# 8_-DAC_and_MIC.net
KiCad netlist of a schematic drawn in Altium Designer
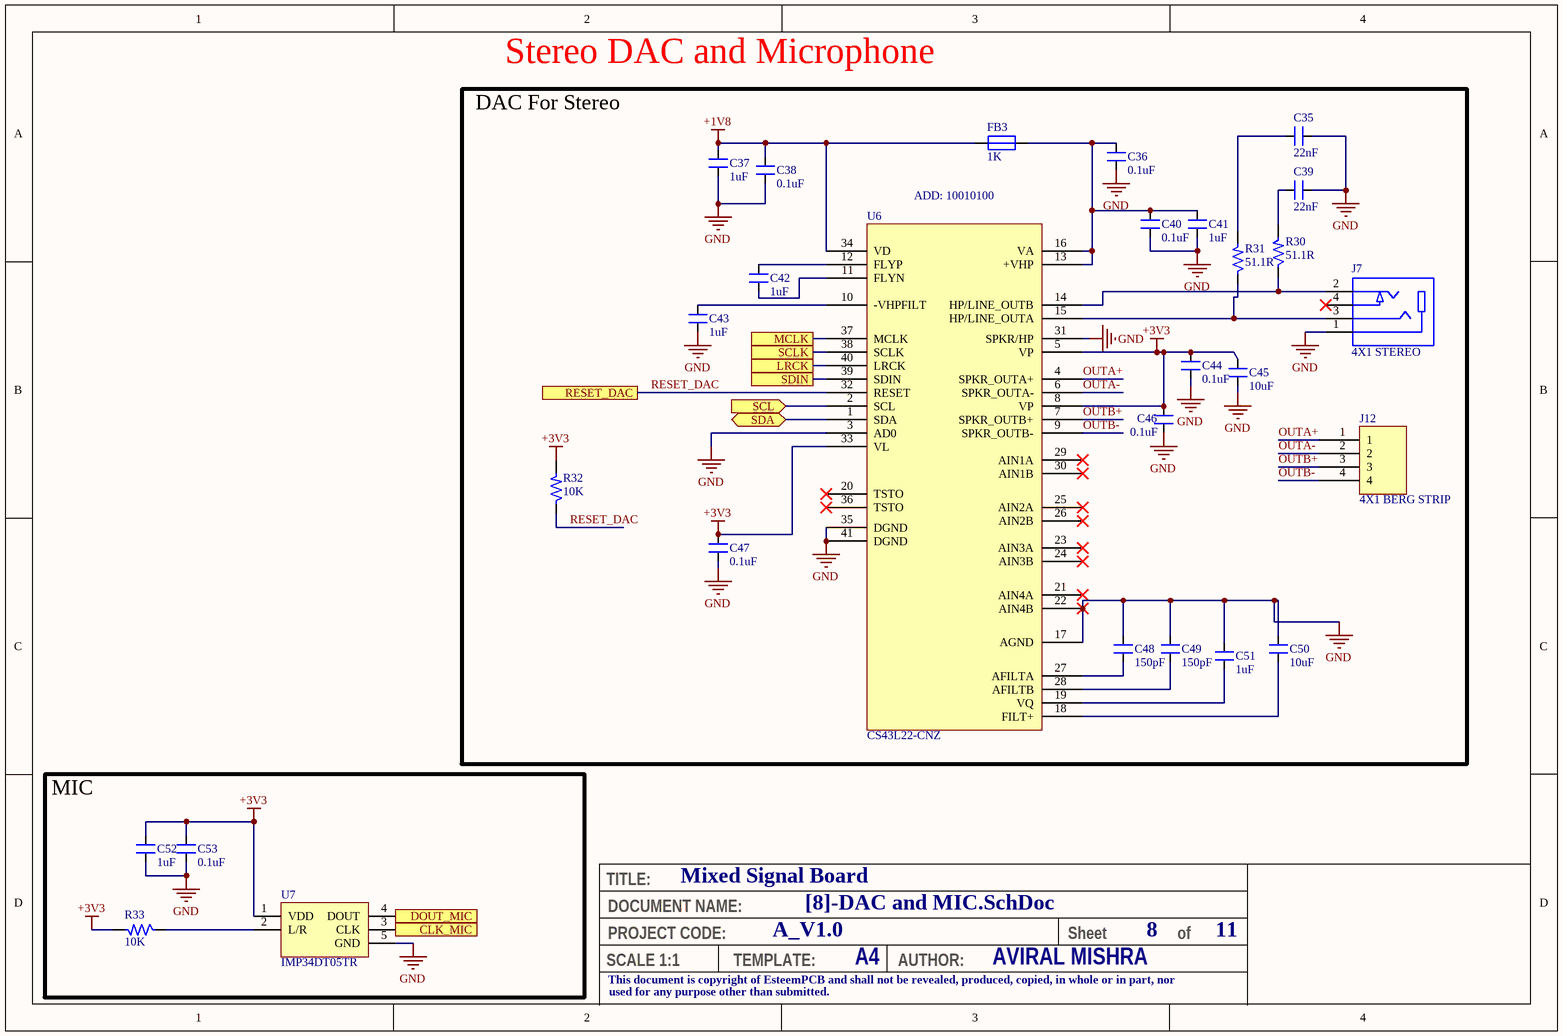
[diagram p0: [8]-DAC and MIC.SchDoc]

(export (version "E")
  (design (tool "Eeschema 10.0.6"))
  (components
    (comp (ref "C35")
      (value "22nF")
      (footprint "CAP_0805")
      (description "0.022µF ±10% 50V Ceramic Capacitor X7R 0805 (2012 Metric)")
      (fields
        (field (name "MANUFACTURER") "Samsung Electro-Mechanics")
        (field (name "MANUFACTURER PART NUMBER") "CL21B223KBANNNC")
      )
      (libsource (lib "ESTEEMPCBLIB") (part "CAP_22nF-50V-10%-0805"))
    )
    (comp (ref "C36")
      (value "0.1uF")
      (footprint "CAP_0805")
      (description "0.1µF ±10% 50V Ceramic Capacitor X7R 0805 (2012 Metric)")
      (fields
        (field (name "MANUFACTURER") "Samsung")
        (field (name "MANUFACTURER PART NUMBER") "CL21B104KBCNNNC")
      )
      (libsource (lib "ESTEEMPCBLIB") (part "CAP_0.1uF-50V-10%-0805"))
    )
    (comp (ref "C37")
      (value "1uF")
      (footprint "CAP_0805")
      (description "1µF ±5% 50V Ceramic Capacitor X7R 0805 (2012 Metric)")
      (fields
        (field (name "MANUFACTURER") "Samsung")
        (field (name "MANUFACTURER PART NUMBER") "CC0805JKX7R9BB105")
      )
      (libsource (lib "ESTEEMPCBLIB") (part "CAP_1uF-50V-5%-0805"))
    )
    (comp (ref "C38")
      (value "0.1uF")
      (footprint "CAP_0805")
      (description "0.1µF ±10% 50V Ceramic Capacitor X7R 0805 (2012 Metric)")
      (fields
        (field (name "MANUFACTURER") "Samsung")
        (field (name "MANUFACTURER PART NUMBER") "CL21B104KBCNNNC")
      )
      (libsource (lib "ESTEEMPCBLIB") (part "CAP_0.1uF-50V-10%-0805"))
    )
    (comp (ref "C39")
      (value "22nF")
      (footprint "CAP_0805")
      (description "0.022µF ±10% 50V Ceramic Capacitor X7R 0805 (2012 Metric)")
      (fields
        (field (name "MANUFACTURER") "Samsung Electro-Mechanics")
        (field (name "MANUFACTURER PART NUMBER") "CL21B223KBANNNC")
      )
      (libsource (lib "ESTEEMPCBLIB") (part "CAP_22nF-50V-10%-0805"))
    )
    (comp (ref "C40")
      (value "0.1uF")
      (footprint "CAP_0805")
      (description "0.1µF ±10% 50V Ceramic Capacitor X7R 0805 (2012 Metric)")
      (fields
        (field (name "MANUFACTURER") "Samsung")
        (field (name "MANUFACTURER PART NUMBER") "CL21B104KBCNNNC")
      )
      (libsource (lib "ESTEEMPCBLIB") (part "CAP_0.1uF-50V-10%-0805"))
    )
    (comp (ref "C41")
      (value "1uF")
      (footprint "CAP_0805")
      (description "1µF ±5% 50V Ceramic Capacitor X7R 0805 (2012 Metric)")
      (fields
        (field (name "MANUFACTURER") "Samsung")
        (field (name "MANUFACTURER PART NUMBER") "CC0805JKX7R9BB105")
      )
      (libsource (lib "ESTEEMPCBLIB") (part "CAP_1uF-50V-5%-0805"))
    )
    (comp (ref "C42")
      (value "1uF")
      (footprint "CAP_0805")
      (description "1µF ±5% 50V Ceramic Capacitor X7R 0805 (2012 Metric)")
      (fields
        (field (name "MANUFACTURER") "Samsung")
        (field (name "MANUFACTURER PART NUMBER") "CC0805JKX7R9BB105")
      )
      (libsource (lib "ESTEEMPCBLIB") (part "CAP_1uF-50V-5%-0805"))
    )
    (comp (ref "C43")
      (value "1uF")
      (footprint "CAP_0805")
      (description "1µF ±5% 50V Ceramic Capacitor X7R 0805 (2012 Metric)")
      (fields
        (field (name "MANUFACTURER") "Samsung")
        (field (name "MANUFACTURER PART NUMBER") "CC0805JKX7R9BB105")
      )
      (libsource (lib "ESTEEMPCBLIB") (part "CAP_1uF-50V-5%-0805"))
    )
    (comp (ref "C44")
      (value "0.1uF")
      (footprint "CAP_0805")
      (description "0.1µF ±10% 50V Ceramic Capacitor X7R 0805 (2012 Metric)")
      (fields
        (field (name "MANUFACTURER") "Samsung")
        (field (name "MANUFACTURER PART NUMBER") "CL21B104KBCNNNC")
      )
      (libsource (lib "ESTEEMPCBLIB") (part "CAP_0.1uF-50V-10%-0805"))
    )
    (comp (ref "C45")
      (value "10uF")
      (footprint "CAP_1206")
      (description "10µF ±10% 50V Ceramic Capacitor X7R 1206 (3216 Metric)")
      (fields
        (field (name "MANUFACTURER") "KEMET")
        (field (name "MANUFACTURER PART NUMBER") "CL31B106KBHNNNE")
      )
      (libsource (lib "ESTEEMPCBLIB") (part "CAP_10uF-50V-10%-1206"))
    )
    (comp (ref "C46")
      (value "0.1uF")
      (footprint "CAP_0805")
      (description "0.1µF ±10% 50V Ceramic Capacitor X7R 0805 (2012 Metric)")
      (fields
        (field (name "MANUFACTURER") "Samsung")
        (field (name "MANUFACTURER PART NUMBER") "CL21B104KBCNNNC")
      )
      (libsource (lib "ESTEEMPCBLIB") (part "CAP_0.1uF-50V-10%-0805"))
    )
    (comp (ref "C47")
      (value "0.1uF")
      (footprint "CAP_0805")
      (description "0.1µF ±10% 50V Ceramic Capacitor X7R 0805 (2012 Metric)")
      (fields
        (field (name "MANUFACTURER") "Samsung")
        (field (name "MANUFACTURER PART NUMBER") "CL21B104KBCNNNC")
      )
      (libsource (lib "ESTEEMPCBLIB") (part "CAP_0.1uF-50V-10%-0805"))
    )
    (comp (ref "C48")
      (value "150pF")
      (footprint "CAP_0805")
      (description "150pF ±10% 50V Ceramic Capacitor C0G, NP0 0805 (2012 Metric)")
      (fields
        (field (name "MANUFACTURER") "AVX Corporation")
        (field (name "MANUFACTURER PART NUMBER") "08055A151KAT2A")
      )
      (libsource (lib "ESTEEMPCBLIB") (part "CAP_150pF-50V-10%-0805"))
    )
    (comp (ref "C49")
      (value "150pF")
      (footprint "CAP_0805")
      (description "150pF ±10% 50V Ceramic Capacitor C0G, NP0 0805 (2012 Metric)")
      (fields
        (field (name "MANUFACTURER") "AVX Corporation")
        (field (name "MANUFACTURER PART NUMBER") "08055A151KAT2A")
      )
      (libsource (lib "ESTEEMPCBLIB") (part "CAP_150pF-50V-10%-0805"))
    )
    (comp (ref "C50")
      (value "10uF")
      (footprint "CAP_1206")
      (description "10µF ±10% 50V Ceramic Capacitor X7R 1206 (3216 Metric)")
      (fields
        (field (name "MANUFACTURER") "KEMET")
        (field (name "MANUFACTURER PART NUMBER") "CL31B106KBHNNNE")
      )
      (libsource (lib "ESTEEMPCBLIB") (part "CAP_10uF-50V-10%-1206"))
    )
    (comp (ref "C51")
      (value "1uF")
      (footprint "CAP_0805")
      (description "1µF ±5% 50V Ceramic Capacitor X7R 0805 (2012 Metric)")
      (fields
        (field (name "MANUFACTURER") "Samsung")
        (field (name "MANUFACTURER PART NUMBER") "CC0805JKX7R9BB105")
      )
      (libsource (lib "ESTEEMPCBLIB") (part "CAP_1uF-50V-5%-0805"))
    )
    (comp (ref "C52")
      (value "1uF")
      (footprint "CAP_0805")
      (description "1µF ±5% 50V Ceramic Capacitor X7R 0805 (2012 Metric)")
      (fields
        (field (name "MANUFACTURER") "Samsung")
        (field (name "MANUFACTURER PART NUMBER") "CC0805JKX7R9BB105")
      )
      (libsource (lib "ESTEEMPCBLIB") (part "CAP_1uF-50V-5%-0805"))
    )
    (comp (ref "C53")
      (value "0.1uF")
      (footprint "CAP_0805")
      (description "0.1µF ±10% 50V Ceramic Capacitor X7R 0805 (2012 Metric)")
      (fields
        (field (name "MANUFACTURER") "Samsung")
        (field (name "MANUFACTURER PART NUMBER") "CL21B104KBCNNNC")
      )
      (libsource (lib "ESTEEMPCBLIB") (part "CAP_0.1uF-50V-10%-0805"))
    )
    (comp (ref "FB3")
      (value "1K")
      (footprint "IND_0805")
      (description "1 kOhms @ 100MHz 1 Power Line Ferrite Bead 0805 (2012 Metric) 1.6A")
      (fields
        (field (name "MANUFACTURER") "Laird")
        (field (name "MANUFACTURER PART NUMBER") "BLM21SP102SH1D")
      )
      (libsource (lib "ESTEEMPCBLIB") (part "FB_1K-100MHZ-1.6A-0805"))
    )
    (comp (ref "J7")
      (value "4X1 STEREO")
      (footprint "CON_SJ-2504A-SMT-TR_SMD")
      (fields
        (field (name "MANUFACTURER") "CUI Devices")
        (field (name "MANUFACTURER PART NUMBER") "SJ-2504A-SMT-TR")
      )
      (libsource (lib "ESTEEMPCBLIB") (part "CON-PLG-STEREO_4X1-100-RA-SMD"))
    )
    (comp (ref "J12")
      (value "4X1 BERG STRIP")
      (footprint "CON4_100_40D72_TH_ST_MALE")
      (description "4 Pins, 1 Row 2.54mm Pitch, Straight bergstrip, Male")
      (fields (field (name "MANUFACTURER") "NA"))
      (libsource (lib "ESTEEMPCBLIB") (part "CON-BS-PLG_4X1-100-ST-TH"))
    )
    (comp (ref "R30")
      (value "51.1R")
      (footprint "RES_0603")
      (description "51.1 Ohms ±1% 0.1W, 1/10W Chip Resistor 0603 (1608 Metric) Thick Film")
      (fields
        (field (name "MANUFACTURER") "Vishay Dale")
        (field (name "MANUFACTURER PART NUMBER") "CRCW060351R1FKEAC")
      )
      (libsource (lib "ESTEEMPCBLIB") (part "RES_51.1R-0.1W-1%-0603"))
    )
    (comp (ref "R31")
      (value "51.1R")
      (footprint "RES_0603")
      (description "51.1 Ohms ±1% 0.1W, 1/10W Chip Resistor 0603 (1608 Metric) Thick Film")
      (fields
        (field (name "MANUFACTURER") "Vishay Dale")
        (field (name "MANUFACTURER PART NUMBER") "CRCW060351R1FKEAC")
      )
      (libsource (lib "ESTEEMPCBLIB") (part "RES_51.1R-0.1W-1%-0603"))
    )
    (comp (ref "R32")
      (value "10K")
      (footprint "RES_0603")
      (description "10 kOhms ±1% 0.1W, 1/10W Chip Resistor 0603 (1608 Metric) Automotive AEC-Q200 Thick Film")
      (fields (field (name "MANUFACTURER") "Walsin") (field (name "MANUFACTURER PART NUMBER") "WR06X1002FTL"))
      (libsource (lib "ESTEEMPCBLIB") (part "RES_10K-0.1W-1%-0603"))
    )
    (comp (ref "R33")
      (value "10K")
      (footprint "RES_0603")
      (description "10 kOhms ±1% 0.1W, 1/10W Chip Resistor 0603 (1608 Metric) Automotive AEC-Q200 Thick Film")
      (fields (field (name "MANUFACTURER") "Walsin") (field (name "MANUFACTURER PART NUMBER") "WR06X1002FTL"))
      (libsource (lib "ESTEEMPCBLIB") (part "RES_10K-0.1W-1%-0603"))
    )
    (comp (ref "U6")
      (value "CS43L22-CNZ")
      (footprint "QFN40_19_284_33X9_SMD")
      (description "Audio D/A Converter ICs Low Power Stereo DAC w/ClassD Spkr Driver")
      (fields (field (name "MANUFACTURER") "Cirrus Logic"))
      (libsource (lib "ESTEEMPCBLIB") (part "IC_CS43L22"))
    )
    (comp (ref "U7")
      (value "IMP34DT05TR")
      (footprint "HCLGA-4_53_137_15X37_SMD")
      (description "MEMS Microphones AUTO & INDUSTRIAL SENSORS")
      (fields (field (name "MANUFACTURER") "STMicroelectronics"))
      (libsource (lib "ESTEEMPCBLIB") (part "IC_IMP34DT05TR"))
    )
  )
  (nets
    (net (code "1") (name "+1V8") (class "Default")
      (node (ref "C37") (pin "2") (pinfunction "2_2") (pintype "passive"))
      (node (ref "C38") (pin "2") (pinfunction "2_2") (pintype "passive"))
      (node (ref "FB3") (pin "1") (pinfunction "1_1") (pintype "passive"))
      (node (ref "U6") (pin "34") (pinfunction "VD_34") (pintype "passive"))
    )
    (net (code "2") (name "+3V3") (class "Default")
      (node (ref "C44") (pin "2") (pinfunction "2_2") (pintype "passive"))
      (node (ref "C45") (pin "2") (pinfunction "2_2") (pintype "passive"))
      (node (ref "C46") (pin "2") (pinfunction "2_2") (pintype "passive"))
      (node (ref "C47") (pin "2") (pinfunction "2_2") (pintype "passive"))
      (node (ref "C52") (pin "2") (pinfunction "2_2") (pintype "passive"))
      (node (ref "C53") (pin "2") (pinfunction "2_2") (pintype "passive"))
      (node (ref "R32") (pin "2") (pinfunction "2_2") (pintype "passive"))
      (node (ref "R33") (pin "2") (pinfunction "2_2") (pintype "passive"))
      (node (ref "U6") (pin "33") (pinfunction "VL_33") (pintype "passive"))
      (node (ref "U6") (pin "5") (pinfunction "VP_5") (pintype "passive"))
      (node (ref "U6") (pin "8") (pinfunction "VP_8") (pintype "passive"))
      (node (ref "U7") (pin "1") (pinfunction "VDD_1") (pintype "passive"))
    )
    (net (code "3") (name "/CLK_MIC") (class "Default")
      (node (ref "U7") (pin "3") (pinfunction "CLK_3") (pintype "passive"))
    )
    (net (code "4") (name "/DOUT_MIC") (class "Default")
      (node (ref "U7") (pin "4") (pinfunction "DOUT_4") (pintype "passive"))
    )
    (net (code "5") (name "/LRCK") (class "Default")
      (node (ref "U6") (pin "40") (pinfunction "LRCK_40") (pintype "passive"))
    )
    (net (code "6") (name "/MCLK") (class "Default")
      (node (ref "U6") (pin "37") (pinfunction "MCLK_37") (pintype "passive"))
    )
    (net (code "7") (name "/OUTA+") (class "Default")
      (node (ref "J12") (pin "1") (pinfunction "1_1") (pintype "passive"))
      (node (ref "U6") (pin "4") (pinfunction "SPKR_OUTA+_4") (pintype "passive"))
    )
    (net (code "8") (name "/OUTA-") (class "Default")
      (node (ref "J12") (pin "2") (pinfunction "2_2") (pintype "passive"))
      (node (ref "U6") (pin "6") (pinfunction "SPKR_OUTA-_6") (pintype "passive"))
    )
    (net (code "9") (name "/OUTB+") (class "Default")
      (node (ref "J12") (pin "3") (pinfunction "3_3") (pintype "passive"))
      (node (ref "U6") (pin "7") (pinfunction "SPKR_OUTB+_7") (pintype "passive"))
    )
    (net (code "10") (name "/OUTB-") (class "Default")
      (node (ref "J12") (pin "4") (pinfunction "4_4") (pintype "passive"))
      (node (ref "U6") (pin "9") (pinfunction "SPKR_OUTB-_9") (pintype "passive"))
    )
    (net (code "11") (name "/RESET_DAC") (class "Default")
      (node (ref "R32") (pin "1") (pinfunction "1_1") (pintype "passive"))
      (node (ref "U6") (pin "32") (pinfunction "RESET_32") (pintype "passive"))
    )
    (net (code "12") (name "/SCL") (class "Default")
      (node (ref "U6") (pin "2") (pinfunction "SCL_2") (pintype "passive"))
    )
    (net (code "13") (name "/SCLK") (class "Default")
      (node (ref "U6") (pin "38") (pinfunction "SCLK_38") (pintype "passive"))
    )
    (net (code "14") (name "/SDA") (class "Default")
      (node (ref "U6") (pin "1") (pinfunction "SDA_1") (pintype "passive"))
    )
    (net (code "15") (name "/SDIN") (class "Default")
      (node (ref "U6") (pin "39") (pinfunction "SDIN_39") (pintype "passive"))
    )
    (net (code "16") (name "GND") (class "Default")
      (node (ref "C35") (pin "2") (pinfunction "2_2") (pintype "passive"))
      (node (ref "C36") (pin "1") (pinfunction "1_1") (pintype "passive"))
      (node (ref "C37") (pin "1") (pinfunction "1_1") (pintype "passive"))
      (node (ref "C38") (pin "1") (pinfunction "1_1") (pintype "passive"))
      (node (ref "C39") (pin "2") (pinfunction "2_2") (pintype "passive"))
      (node (ref "C40") (pin "1") (pinfunction "1_1") (pintype "passive"))
      (node (ref "C41") (pin "1") (pinfunction "1_1") (pintype "passive"))
      (node (ref "C43") (pin "1") (pinfunction "1_1") (pintype "passive"))
      (node (ref "C44") (pin "1") (pinfunction "1_1") (pintype "passive"))
      (node (ref "C45") (pin "1") (pinfunction "1_1") (pintype "passive"))
      (node (ref "C46") (pin "1") (pinfunction "1_1") (pintype "passive"))
      (node (ref "C47") (pin "1") (pinfunction "1_1") (pintype "passive"))
      (node (ref "C48") (pin "2") (pinfunction "2_2") (pintype "passive"))
      (node (ref "C49") (pin "2") (pinfunction "2_2") (pintype "passive"))
      (node (ref "C50") (pin "2") (pinfunction "2_2") (pintype "passive"))
      (node (ref "C51") (pin "2") (pinfunction "2_2") (pintype "passive"))
      (node (ref "C52") (pin "1") (pinfunction "1_1") (pintype "passive"))
      (node (ref "C53") (pin "1") (pinfunction "1_1") (pintype "passive"))
      (node (ref "J7") (pin "1") (pinfunction "1_1") (pintype "passive"))
      (node (ref "U6") (pin "17") (pinfunction "AGND_17") (pintype "passive"))
      (node (ref "U6") (pin "22") (pinfunction "AIN4B_22") (pintype "passive"))
      (node (ref "U6") (pin "3") (pinfunction "AD0_3") (pintype "passive"))
      (node (ref "U6") (pin "31") (pinfunction "SPKR/HP_31") (pintype "passive"))
      (node (ref "U6") (pin "35") (pinfunction "DGND_35") (pintype "passive"))
      (node (ref "U6") (pin "41") (pinfunction "DGND_41") (pintype "passive"))
      (node (ref "U7") (pin "5") (pinfunction "GND_5") (pintype "passive"))
    )
    (net (code "17") (name "Net-(C35-Pad1)") (class "Default")
      (node (ref "C35") (pin "1") (pinfunction "1_1") (pintype "passive"))
      (node (ref "R31") (pin "2") (pinfunction "2_2") (pintype "passive"))
    )
    (net (code "18") (name "Net-(C39-Pad1)") (class "Default")
      (node (ref "C39") (pin "1") (pinfunction "1_1") (pintype "passive"))
      (node (ref "R30") (pin "2") (pinfunction "2_2") (pintype "passive"))
    )
    (net (code "19") (name "Net-(U6-+VHP)") (class "Default")
      (node (ref "C36") (pin "2") (pinfunction "2_2") (pintype "passive"))
      (node (ref "C40") (pin "2") (pinfunction "2_2") (pintype "passive"))
      (node (ref "C41") (pin "2") (pinfunction "2_2") (pintype "passive"))
      (node (ref "FB3") (pin "2") (pinfunction "2_2") (pintype "passive"))
      (node (ref "U6") (pin "13") (pinfunction "+VHP_13") (pintype "passive"))
      (node (ref "U6") (pin "16") (pinfunction "VA_16") (pintype "passive"))
    )
    (net (code "20") (name "Net-(U6--VHPFILT)") (class "Default")
      (node (ref "C43") (pin "2") (pinfunction "2_2") (pintype "passive"))
      (node (ref "U6") (pin "10") (pinfunction "-VHPFILT_10") (pintype "passive"))
    )
    (net (code "21") (name "Net-(U6-AFILTA)") (class "Default")
      (node (ref "C48") (pin "1") (pinfunction "1_1") (pintype "passive"))
      (node (ref "U6") (pin "27") (pinfunction "AFILTA_27") (pintype "passive"))
    )
    (net (code "22") (name "Net-(U6-AFILTB)") (class "Default")
      (node (ref "C49") (pin "1") (pinfunction "1_1") (pintype "passive"))
      (node (ref "U6") (pin "28") (pinfunction "AFILTB_28") (pintype "passive"))
    )
    (net (code "23") (name "Net-(U6-FILT+)") (class "Default")
      (node (ref "C50") (pin "1") (pinfunction "1_1") (pintype "passive"))
      (node (ref "U6") (pin "18") (pinfunction "FILT+_18") (pintype "passive"))
    )
    (net (code "24") (name "Net-(U6-FLYN)") (class "Default")
      (node (ref "C42") (pin "1") (pinfunction "1_1") (pintype "passive"))
      (node (ref "U6") (pin "11") (pinfunction "FLYN_11") (pintype "passive"))
    )
    (net (code "25") (name "Net-(U6-FLYP)") (class "Default")
      (node (ref "C42") (pin "2") (pinfunction "2_2") (pintype "passive"))
      (node (ref "U6") (pin "12") (pinfunction "FLYP_12") (pintype "passive"))
    )
    (net (code "26") (name "Net-(U6-HP{slash}LINE_OUTA)") (class "Default")
      (node (ref "J7") (pin "3") (pinfunction "3_3") (pintype "passive"))
      (node (ref "R31") (pin "1") (pinfunction "1_1") (pintype "passive"))
      (node (ref "U6") (pin "15") (pinfunction "HP/LINE_OUTA_15") (pintype "passive"))
    )
    (net (code "27") (name "Net-(U6-HP{slash}LINE_OUTB)") (class "Default")
      (node (ref "J7") (pin "2") (pinfunction "2_2") (pintype "passive"))
      (node (ref "R30") (pin "1") (pinfunction "1_1") (pintype "passive"))
      (node (ref "U6") (pin "14") (pinfunction "HP/LINE_OUTB_14") (pintype "passive"))
    )
    (net (code "28") (name "Net-(U6-VQ)") (class "Default")
      (node (ref "C51") (pin "1") (pinfunction "1_1") (pintype "passive"))
      (node (ref "U6") (pin "19") (pinfunction "VQ_19") (pintype "passive"))
    )
    (net (code "29") (name "Net-(U7-L{slash}R)") (class "Default")
      (node (ref "R33") (pin "1") (pinfunction "1_1") (pintype "passive"))
      (node (ref "U7") (pin "2") (pinfunction "L/R_2") (pintype "passive"))
    )
    (net (code "30") (name "unconnected-(J7-Pad4)") (class "Default")
      (node (ref "J7") (pin "4") (pinfunction "4_4") (pintype "passive+no_connect"))
    )
    (net (code "31") (name "unconnected-(U6-AIN1A-Pad29)") (class "Default")
      (node (ref "U6") (pin "29") (pinfunction "AIN1A_29") (pintype "passive+no_connect"))
    )
    (net (code "32") (name "unconnected-(U6-AIN1B-Pad30)") (class "Default")
      (node (ref "U6") (pin "30") (pinfunction "AIN1B_30") (pintype "passive+no_connect"))
    )
    (net (code "33") (name "unconnected-(U6-AIN2A-Pad25)") (class "Default")
      (node (ref "U6") (pin "25") (pinfunction "AIN2A_25") (pintype "passive+no_connect"))
    )
    (net (code "34") (name "unconnected-(U6-AIN2B-Pad26)") (class "Default")
      (node (ref "U6") (pin "26") (pinfunction "AIN2B_26") (pintype "passive+no_connect"))
    )
    (net (code "35") (name "unconnected-(U6-AIN3A-Pad23)") (class "Default")
      (node (ref "U6") (pin "23") (pinfunction "AIN3A_23") (pintype "passive+no_connect"))
    )
    (net (code "36") (name "unconnected-(U6-AIN3B-Pad24)") (class "Default")
      (node (ref "U6") (pin "24") (pinfunction "AIN3B_24") (pintype "passive+no_connect"))
    )
    (net (code "37") (name "unconnected-(U6-AIN4A-Pad21)") (class "Default")
      (node (ref "U6") (pin "21") (pinfunction "AIN4A_21") (pintype "passive+no_connect"))
    )
    (net (code "38") (name "unconnected-(U6-TSTO-Pad20)") (class "Default")
      (node (ref "U6") (pin "20") (pinfunction "TSTO_20") (pintype "passive+no_connect"))
    )
    (net (code "39") (name "unconnected-(U6-TSTO-Pad36)") (class "Default")
      (node (ref "U6") (pin "36") (pinfunction "TSTO_36") (pintype "passive+no_connect"))
    )
  )
)
